# Sense_Plates.net
KiCad netlist of a schematic drawn in Altium Designer
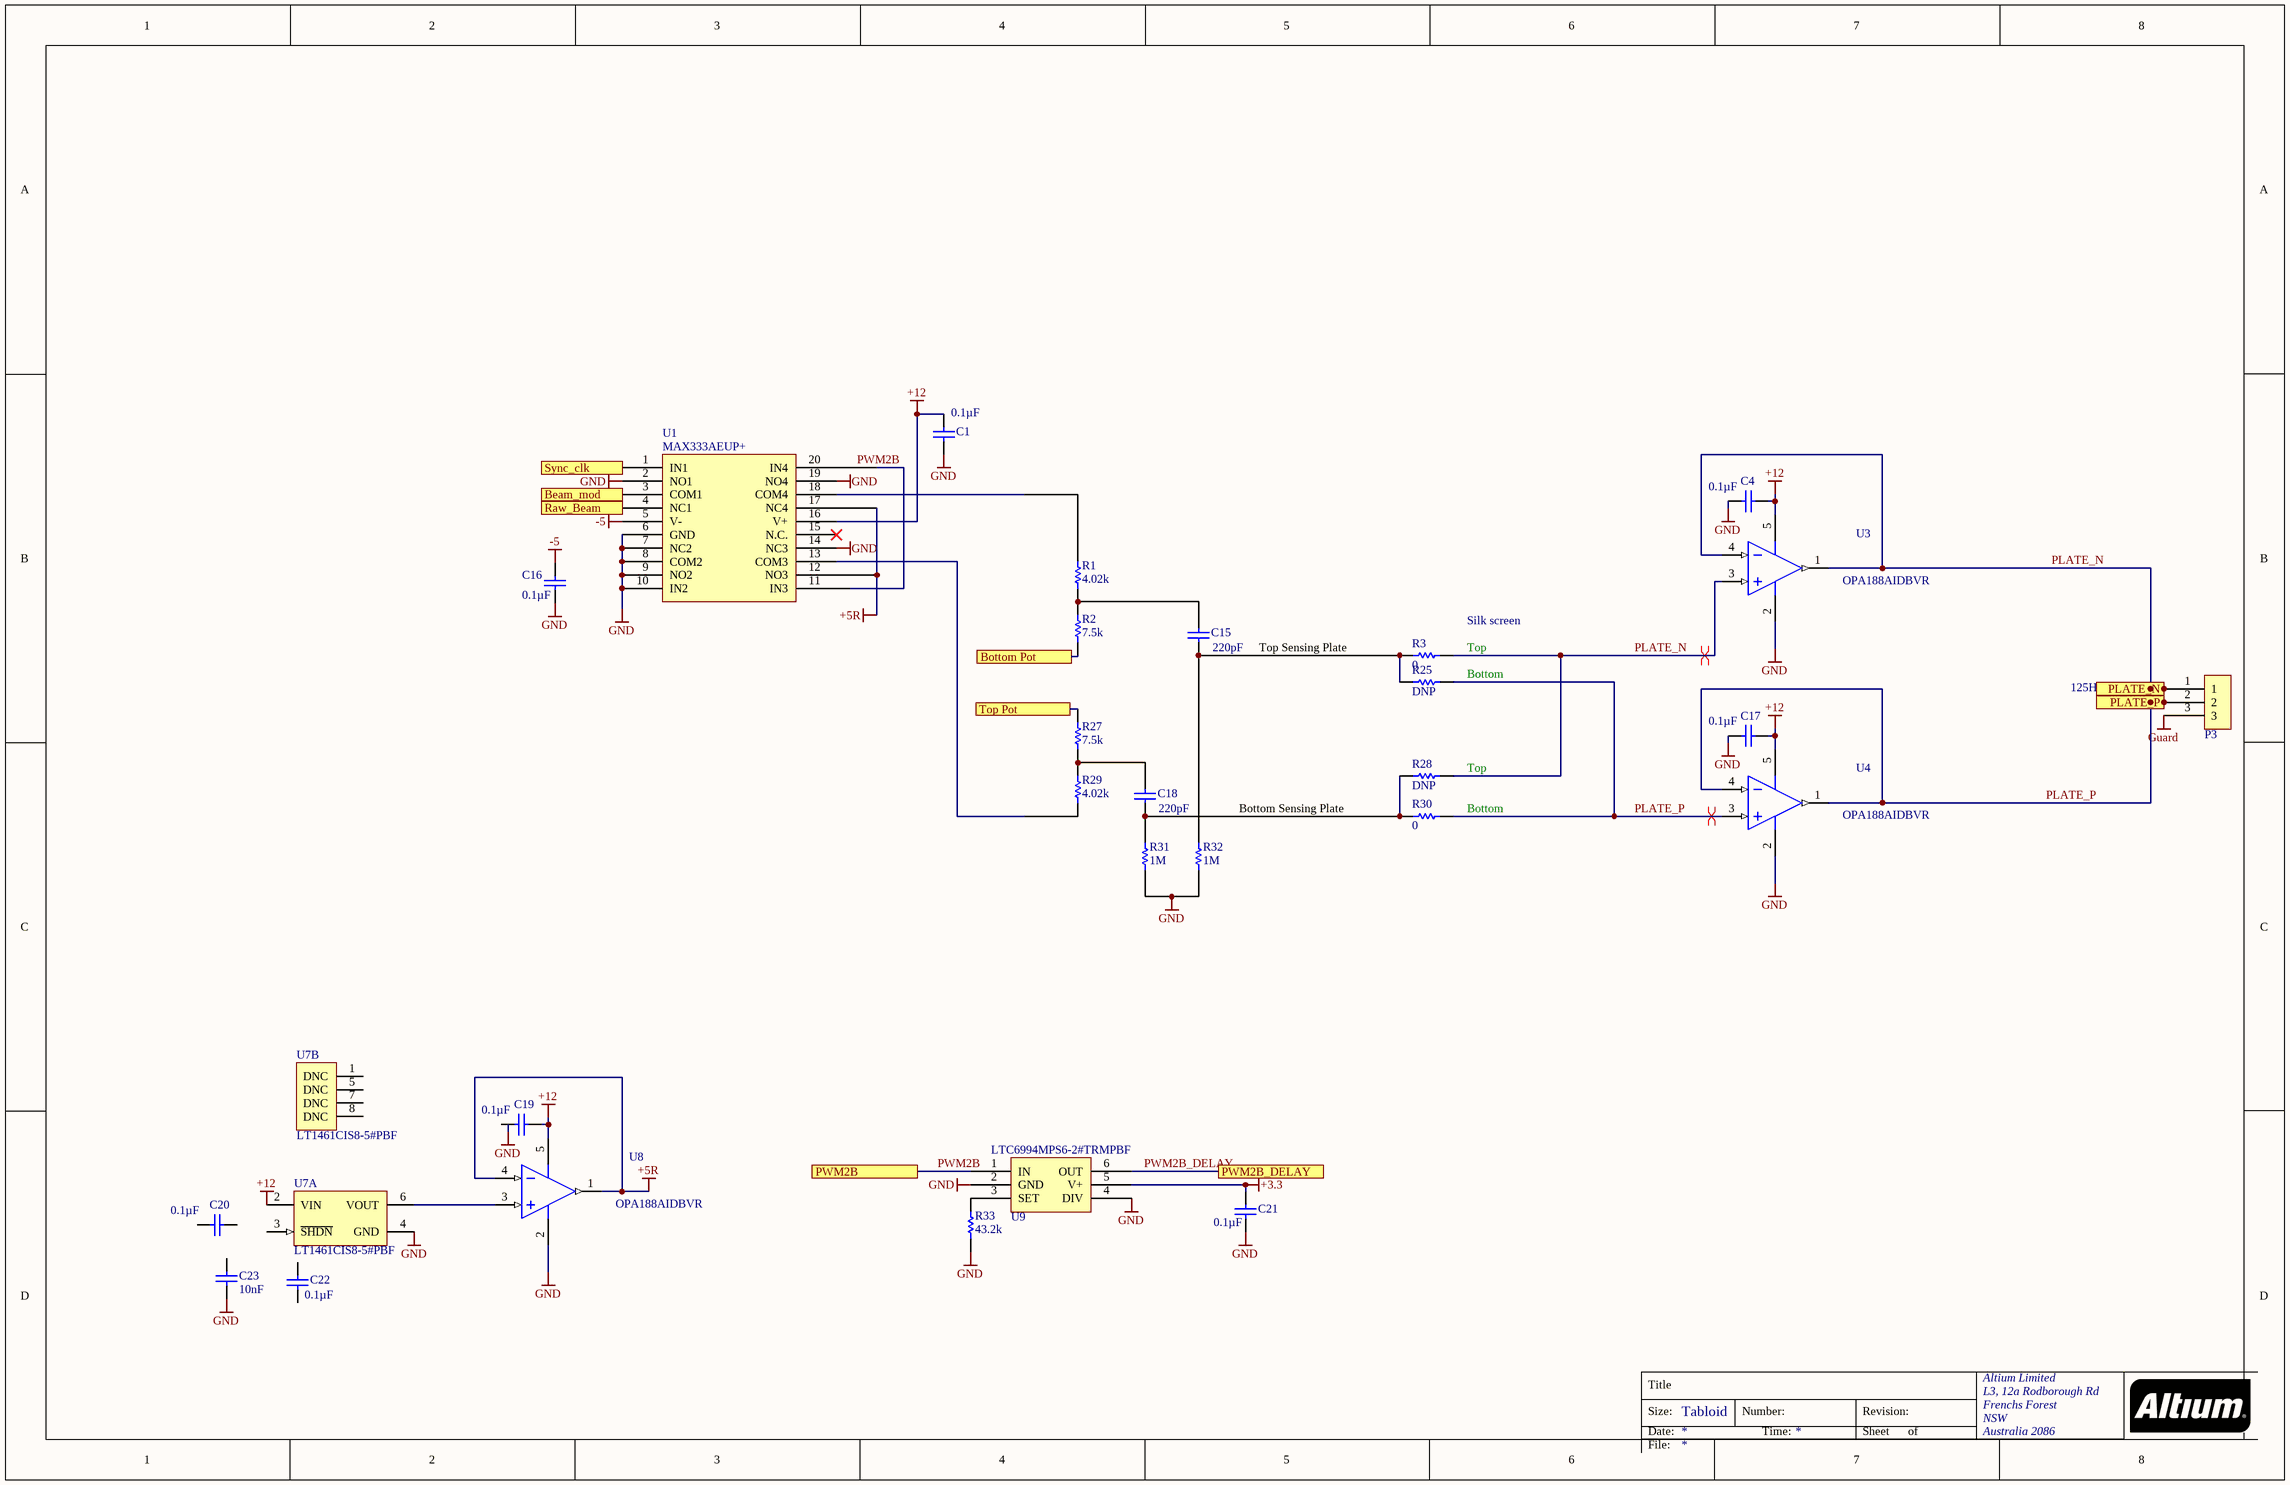
[diagram p0: Sense_Plates.SchDoc]

(export (version "E")
  (design (tool "Eeschema 10.0.6"))
  (components
    (comp (ref "C1")
      (value "CAP CER 0.1UF 25V X7R 0805")
      (footprint "CAPC0805(2012)145_N")
      (fields
        (field (name "MANUFACTURER") "Murata Electronics North America")
        (field (name "MANUFACTURER PART NUMBER") "GRM21BR71E104KA01L")
        (field (name "CAPACITANCE") "0.1µF")
        (field (name "TOLERANCE") "±10%")
      )
      (libsource (lib "Altium Content Vault") (part "CMP-1036-04795-1"))
    )
    (comp (ref "C4")
      (value "CAP CER 0.1UF 25V X7R 0805")
      (footprint "CAPC0805(2012)145_N")
      (fields
        (field (name "MANUFACTURER") "Murata Electronics North America")
        (field (name "MANUFACTURER PART NUMBER") "GRM21BR71E104KA01L")
        (field (name "CAPACITANCE") "0.1µF")
        (field (name "TOLERANCE") "±10%")
      )
      (libsource (lib "Altium Content Vault") (part "CMP-1036-04795-1"))
    )
    (comp (ref "C15")
      (value "CAP CER 1UF 25V X7R 0805")
      (footprint "CAPC0805(2012)155_L")
      (fields
        (field (name "MANUFACTURER") "Murata Electronics North America")
        (field (name "MANUFACTURER PART NUMBER") "GRM21BR71E105KA99L")
        (field (name "CAPACITANCE") "220pF")
        (field (name "TOLERANCE") "±10%")
      )
      (libsource (lib "Altium Content Vault") (part "CMP-1036-04882-1"))
    )
    (comp (ref "C16")
      (value "CAP CER 0.1UF 25V X7R 0805")
      (footprint "CAPC0805(2012)145_N")
      (fields
        (field (name "MANUFACTURER") "Murata Electronics North America")
        (field (name "MANUFACTURER PART NUMBER") "GRM21BR71E104KA01L")
        (field (name "CAPACITANCE") "0.1µF")
        (field (name "TOLERANCE") "±10%")
      )
      (libsource (lib "Altium Content Vault") (part "CMP-1036-04795-1"))
    )
    (comp (ref "C17")
      (value "CAP CER 0.1UF 25V X7R 0805")
      (footprint "CAPC0805(2012)145_N")
      (fields
        (field (name "MANUFACTURER") "Murata Electronics North America")
        (field (name "MANUFACTURER PART NUMBER") "GRM21BR71E104KA01L")
        (field (name "CAPACITANCE") "0.1µF")
        (field (name "TOLERANCE") "±10%")
      )
      (libsource (lib "Altium Content Vault") (part "CMP-1036-04795-1"))
    )
    (comp (ref "C18")
      (value "CAP CER 1UF 25V X7R 0805")
      (footprint "CAPC0805(2012)155_L")
      (fields
        (field (name "MANUFACTURER") "Murata Electronics North America")
        (field (name "MANUFACTURER PART NUMBER") "GRM21BR71E105KA99L")
        (field (name "CAPACITANCE") "220pF")
        (field (name "TOLERANCE") "±10%")
      )
      (libsource (lib "Altium Content Vault") (part "CMP-1036-04882-1"))
    )
    (comp (ref "C19")
      (value "CAP CER 0.1UF 25V X7R 0805")
      (footprint "CAPC0805(2012)145_N")
      (fields
        (field (name "MANUFACTURER") "Murata Electronics North America")
        (field (name "MANUFACTURER PART NUMBER") "GRM21BR71E104KA01L")
        (field (name "CAPACITANCE") "0.1µF")
        (field (name "TOLERANCE") "±10%")
      )
      (libsource (lib "Altium Content Vault") (part "CMP-1036-04795-1"))
    )
    (comp (ref "C20")
      (value "CAP CER 0.1UF 25V X7R 0805")
      (footprint "CAPC0805(2012)145_N")
      (fields
        (field (name "MANUFACTURER") "Murata Electronics North America")
        (field (name "MANUFACTURER PART NUMBER") "GRM21BR71E104KA01L")
        (field (name "CAPACITANCE") "0.1µF")
        (field (name "TOLERANCE") "±10%")
      )
      (libsource (lib "Altium Content Vault") (part "CMP-1036-04795-1"))
    )
    (comp (ref "C21")
      (value "CAP CER 0.1UF 25V X7R 0805")
      (footprint "CAPC0805(2012)145_N")
      (fields
        (field (name "MANUFACTURER") "Murata Electronics North America")
        (field (name "MANUFACTURER PART NUMBER") "GRM21BR71E104KA01L")
        (field (name "CAPACITANCE") "0.1µF")
        (field (name "TOLERANCE") "±10%")
      )
      (libsource (lib "Altium Content Vault") (part "CMP-1036-04795-1"))
    )
    (comp (ref "C22")
      (value "CAP CER 0.1UF 25V X7R 0805")
      (footprint "CAPC0805(2012)145_N")
      (fields
        (field (name "MANUFACTURER") "Murata Electronics North America")
        (field (name "MANUFACTURER PART NUMBER") "GRM21BR71E104KA01L")
        (field (name "CAPACITANCE") "0.1µF")
        (field (name "TOLERANCE") "±10%")
      )
      (libsource (lib "Altium Content Vault") (part "CMP-1036-04795-1"))
    )
    (comp (ref "C23")
      (value "Multilayer Ceramic Capacitors MLCC - SMD/SMT 0.01uF 50volts 10% X7R")
      (footprint "CAPC0805(2012)145_N")
      (fields
        (field (name "MANUFACTURER") "Kemet")
        (field (name "MANUFACTURER PART NUMBER") "C0805C103K5RACAUTO")
        (field (name "CAPACITANCE") "10nF")
        (field (name "TOLERANCE") "10%")
      )
      (libsource (lib "Altium Content Vault") (part "CMP-1036-04795-1"))
    )
    (comp (ref "P3")
      (value "Triax_Conn")
      (footprint "Triax_Conn")
      (libsource (lib "ZLS_Schematic_lib") (part "Triax_Conn"))
    )
    (comp (ref "R1")
      (value "4.02k")
      (footprint "RESC0402(1005)_M")
      (libsource (lib "Altium Content Vault") (part "CMP-1011-00463-1"))
    )
    (comp (ref "R2")
      (value "7.5k")
      (footprint "RESC0402(1005)_M")
      (libsource (lib "Altium Content Vault") (part "CMP-1011-00463-1"))
    )
    (comp (ref "R3")
      (value "0")
      (footprint "RESC0402(1005)_M")
      (libsource (lib "Altium Content Vault") (part "CMP-1011-00463-1"))
    )
    (comp (ref "R25")
      (value "DNP")
      (footprint "RESC0402(1005)_M")
      (libsource (lib "Altium Content Vault") (part "CMP-1011-00463-1"))
    )
    (comp (ref "R27")
      (value "7.5k")
      (footprint "RESC0402(1005)_M")
      (libsource (lib "Altium Content Vault") (part "CMP-1011-00463-1"))
    )
    (comp (ref "R28")
      (value "DNP")
      (footprint "RESC0402(1005)_M")
      (libsource (lib "Altium Content Vault") (part "CMP-1011-00463-1"))
    )
    (comp (ref "R29")
      (value "4.02k")
      (footprint "RESC0402(1005)_M")
      (libsource (lib "Altium Content Vault") (part "CMP-1011-00463-1"))
    )
    (comp (ref "R30")
      (value "0")
      (footprint "RESC0402(1005)_M")
      (libsource (lib "Altium Content Vault") (part "CMP-1011-00463-1"))
    )
    (comp (ref "R31")
      (value "1M")
      (footprint "RESC0402(1005)_M")
      (libsource (lib "Altium Content Vault") (part "CMP-1011-00463-1"))
    )
    (comp (ref "R32")
      (value "1M")
      (footprint "RESC0402(1005)_M")
      (libsource (lib "Altium Content Vault") (part "CMP-1011-00463-1"))
    )
    (comp (ref "R33")
      (value "43.2k")
      (footprint "RESC0402(1005)_M")
      (libsource (lib "Altium Content Vault") (part "CMP-1011-00463-1"))
    )
    (comp (ref "U1")
      (value "MAX333AEUP+")
      (footprint "TSOP65P640X90-20N")
      (description "IC SWITCH QUAD SPDT 20TSSOP")
      (fields (field (name "MANUFACTURER") "Maxim Integrated") (field (name "BASE PART NUMBER") "MAX333"))
      (libsource (lib "ZLS_Schematic_lib") (part "MAX333CWP+"))
    )
    (comp (ref "U3")
      (value "OPA188AIDBVR")
      (footprint "DBV0005A_M")
      (fields (field (name "MANUFACTURER") "Texas Instruments"))
      (libsource (lib "Altium Content Vault") (part "CMP-0809-00005-2"))
    )
    (comp (ref "U4")
      (value "OPA188AIDBVR")
      (footprint "DBV0005A_M")
      (fields (field (name "MANUFACTURER") "Texas Instruments"))
      (libsource (lib "Altium Content Vault") (part "CMP-0809-00005-2"))
    )
    (comp (ref "U7")
      (value "LT1461CIS8-5#PBF")
      (footprint "LT-S8-8_L")
      (description "Micropower Precision Low Dropout Voltage Reference, 5 V, -40 to 85 degC, 8-Pin SOIC, RoHS, Tube")
      (fields (field (name "TOLERANCE") "±0.08%") (field (name "MANUFACTURER") "Linear Technology"))
      (libsource (lib "Altium Content Vault") (part "LT-LT1461-S8"))
    )
    (comp (ref "U8")
      (value "OPA188AIDBVR")
      (footprint "DBV0005A_M")
      (fields (field (name "MANUFACTURER") "Texas Instruments"))
      (libsource (lib "Altium Content Vault") (part "CMP-0809-00005-2"))
    )
    (comp (ref "U9")
      (value "LTC6994MPS6-2#TRMPBF")
      (footprint "LTC6994MPS6-2#TRMPBF")
      (description "IC DELAY BLOCK 8TAP PROG TSOT23")
      (fields
        (field (name "MANUFACTURER") "Linear Technology/Analog Devices")
        (field (name "MANUFACTURER PART NUMBER") "LTC6994CS6-2#TRMPBF")
      )
      (libsource (lib "ZLS_Schematic_lib") (part "LTC6994MPS6-2#TRMPBF"))
    )
  )
  (nets
    (net (code "1") (name "+3.3") (class "Default")
      (node (ref "C21") (pin "1") (pinfunction "1_1") (pintype "passive"))
      (node (ref "U9") (pin "5") (pinfunction "V+_5") (pintype "passive"))
    )
    (net (code "2") (name "+5R") (class "Default")
      (node (ref "U1") (pin "12") (pinfunction "NO3_12") (pintype "passive"))
      (node (ref "U1") (pin "17") (pinfunction "NC4_17") (pintype "passive"))
      (node (ref "U8") (pin "1") (pinfunction "OUT_1") (pintype "output"))
      (node (ref "U8") (pin "4") (pinfunction "IN-_4") (pintype "input"))
    )
    (net (code "3") (name "+12") (class "Default")
      (node (ref "C1") (pin "1") (pinfunction "1_1") (pintype "passive"))
      (node (ref "C17") (pin "2") (pinfunction "2_2") (pintype "passive"))
      (node (ref "C19") (pin "2") (pinfunction "2_2") (pintype "passive"))
      (node (ref "C4") (pin "2") (pinfunction "2_2") (pintype "passive"))
      (node (ref "U1") (pin "16") (pinfunction "V+_16") (pintype "power_in"))
      (node (ref "U3") (pin "5") (pinfunction "V+_5") (pintype "power_in"))
      (node (ref "U4") (pin "5") (pinfunction "V+_5") (pintype "power_in"))
      (node (ref "U7") (pin "2") (pinfunction "VIN_2") (pintype "power_in"))
      (node (ref "U8") (pin "5") (pinfunction "V+_5") (pintype "power_in"))
    )
    (net (code "4") (name "-5") (class "Default")
      (node (ref "C16") (pin "1") (pinfunction "1_1") (pintype "passive"))
      (node (ref "U1") (pin "5") (pinfunction "V-_5") (pintype "power_in"))
    )
    (net (code "5") (name "/Beam_mod") (class "Default")
      (node (ref "U1") (pin "3") (pinfunction "COM1_3") (pintype "passive"))
    )
    (net (code "6") (name "/Bottom Pot") (class "Default")
      (node (ref "R2") (pin "1") (pinfunction "1_1") (pintype "passive"))
    )
    (net (code "7") (name "/PLATE_N") (class "Default")
      (node (ref "P3") (pin "1") (pinfunction "1_1") (pintype "passive"))
      (node (ref "R28") (pin "1") (pinfunction "1_1") (pintype "passive"))
      (node (ref "R3") (pin "1") (pinfunction "1_1") (pintype "passive"))
      (node (ref "U3") (pin "1") (pinfunction "OUT_1") (pintype "output"))
      (node (ref "U3") (pin "3") (pinfunction "IN+_3") (pintype "input"))
      (node (ref "U3") (pin "4") (pinfunction "IN-_4") (pintype "input"))
    )
    (net (code "8") (name "/PLATE_P") (class "Default")
      (node (ref "P3") (pin "2") (pinfunction "2_2") (pintype "passive"))
      (node (ref "R25") (pin "1") (pinfunction "1_1") (pintype "passive"))
      (node (ref "R30") (pin "1") (pinfunction "1_1") (pintype "passive"))
      (node (ref "U4") (pin "1") (pinfunction "OUT_1") (pintype "output"))
      (node (ref "U4") (pin "3") (pinfunction "IN+_3") (pintype "input"))
      (node (ref "U4") (pin "4") (pinfunction "IN-_4") (pintype "input"))
    )
    (net (code "9") (name "/PWM2B") (class "Default")
      (node (ref "U1") (pin "11") (pinfunction "IN3_11") (pintype "passive"))
      (node (ref "U1") (pin "20") (pinfunction "IN4_20") (pintype "passive"))
      (node (ref "U9") (pin "1") (pinfunction "IN_1") (pintype "passive"))
    )
    (net (code "10") (name "/PWM2B_DELAY") (class "Default")
      (node (ref "U9") (pin "6") (pinfunction "OUT_6") (pintype "passive"))
    )
    (net (code "11") (name "/Raw_Beam") (class "Default")
      (node (ref "U1") (pin "4") (pinfunction "NC1_4") (pintype "passive"))
    )
    (net (code "12") (name "/Sync_clk") (class "Default")
      (node (ref "U1") (pin "1") (pinfunction "IN1_1") (pintype "passive"))
    )
    (net (code "13") (name "/Top Pot") (class "Default")
      (node (ref "R27") (pin "2") (pinfunction "2_2") (pintype "passive"))
    )
    (net (code "14") (name "GND") (class "Default")
      (node (ref "C1") (pin "2") (pinfunction "2_2") (pintype "passive"))
      (node (ref "C16") (pin "2") (pinfunction "2_2") (pintype "passive"))
      (node (ref "C17") (pin "1") (pinfunction "1_1") (pintype "passive"))
      (node (ref "C21") (pin "2") (pinfunction "2_2") (pintype "passive"))
      (node (ref "C23") (pin "2") (pinfunction "2_2") (pintype "passive"))
      (node (ref "C4") (pin "1") (pinfunction "1_1") (pintype "passive"))
      (node (ref "R31") (pin "1") (pinfunction "1_1") (pintype "passive"))
      (node (ref "R32") (pin "1") (pinfunction "1_1") (pintype "passive"))
      (node (ref "R33") (pin "1") (pinfunction "1_1") (pintype "passive"))
      (node (ref "U1") (pin "10") (pinfunction "IN2_10") (pintype "passive"))
      (node (ref "U1") (pin "14") (pinfunction "NC3_14") (pintype "passive"))
      (node (ref "U1") (pin "19") (pinfunction "NO4_19") (pintype "passive"))
      (node (ref "U1") (pin "2") (pinfunction "NO1_2") (pintype "passive"))
      (node (ref "U1") (pin "6") (pinfunction "GND_6") (pintype "passive"))
      (node (ref "U1") (pin "7") (pinfunction "NC2_7") (pintype "passive"))
      (node (ref "U1") (pin "8") (pinfunction "COM2_8") (pintype "passive"))
      (node (ref "U1") (pin "9") (pinfunction "NO2_9") (pintype "passive"))
      (node (ref "U3") (pin "2") (pinfunction "V-_2") (pintype "power_in"))
      (node (ref "U4") (pin "2") (pinfunction "V-_2") (pintype "power_in"))
      (node (ref "U7") (pin "4") (pinfunction "GND_4") (pintype "power_in"))
      (node (ref "U8") (pin "2") (pinfunction "V-_2") (pintype "power_in"))
      (node (ref "U9") (pin "2") (pinfunction "GND_2") (pintype "passive"))
      (node (ref "U9") (pin "4") (pinfunction "DIV_4") (pintype "passive"))
    )
    (net (code "15") (name "Guard") (class "Default")
      (node (ref "P3") (pin "3") (pinfunction "3_3") (pintype "passive"))
    )
    (net (code "16") (name "Net-(C15-Pad1)") (class "Default")
      (node (ref "C15") (pin "1") (pinfunction "1_1") (pintype "passive"))
      (node (ref "R25") (pin "2") (pinfunction "2_2") (pintype "passive"))
      (node (ref "R3") (pin "2") (pinfunction "2_2") (pintype "passive"))
      (node (ref "R32") (pin "2") (pinfunction "2_2") (pintype "passive"))
    )
    (net (code "17") (name "Net-(C15-Pad2)") (class "Default")
      (node (ref "C15") (pin "2") (pinfunction "2_2") (pintype "passive"))
      (node (ref "R1") (pin "1") (pinfunction "1_1") (pintype "passive"))
      (node (ref "R2") (pin "2") (pinfunction "2_2") (pintype "passive"))
    )
    (net (code "18") (name "Net-(C18-Pad1)") (class "Default")
      (node (ref "C18") (pin "1") (pinfunction "1_1") (pintype "passive"))
      (node (ref "R28") (pin "2") (pinfunction "2_2") (pintype "passive"))
      (node (ref "R30") (pin "2") (pinfunction "2_2") (pintype "passive"))
      (node (ref "R31") (pin "2") (pinfunction "2_2") (pintype "passive"))
    )
    (net (code "19") (name "Net-(C18-Pad2)") (class "Default")
      (node (ref "C18") (pin "2") (pinfunction "2_2") (pintype "passive"))
      (node (ref "R27") (pin "1") (pinfunction "1_1") (pintype "passive"))
      (node (ref "R29") (pin "2") (pinfunction "2_2") (pintype "passive"))
    )
    (net (code "20") (name "Net-(U1-COM3)") (class "Default")
      (node (ref "R29") (pin "1") (pinfunction "1_1") (pintype "passive"))
      (node (ref "U1") (pin "13") (pinfunction "COM3_13") (pintype "passive"))
    )
    (net (code "21") (name "Net-(U1-COM4)") (class "Default")
      (node (ref "R1") (pin "2") (pinfunction "2_2") (pintype "passive"))
      (node (ref "U1") (pin "18") (pinfunction "COM4_18") (pintype "passive"))
    )
    (net (code "22") (name "Net-(U7A-VOUT)") (class "Default")
      (node (ref "U7") (pin "6") (pinfunction "VOUT_6") (pintype "power_in"))
      (node (ref "U8") (pin "3") (pinfunction "IN+_3") (pintype "input"))
    )
    (net (code "23") (name "Net-(U9-SET)") (class "Default")
      (node (ref "R33") (pin "2") (pinfunction "2_2") (pintype "passive"))
      (node (ref "U9") (pin "3") (pinfunction "SET_3") (pintype "passive"))
    )
    (net (code "24") (name "unconnected-(C19-Pad1)") (class "Default")
      (node (ref "C19") (pin "1") (pinfunction "1_1") (pintype "passive"))
    )
    (net (code "25") (name "unconnected-(C20-Pad1)") (class "Default")
      (node (ref "C20") (pin "1") (pinfunction "1_1") (pintype "passive"))
    )
    (net (code "26") (name "unconnected-(C20-Pad2)") (class "Default")
      (node (ref "C20") (pin "2") (pinfunction "2_2") (pintype "passive"))
    )
    (net (code "27") (name "unconnected-(C22-Pad1)") (class "Default")
      (node (ref "C22") (pin "1") (pinfunction "1_1") (pintype "passive"))
    )
    (net (code "28") (name "unconnected-(C22-Pad2)") (class "Default")
      (node (ref "C22") (pin "2") (pinfunction "2_2") (pintype "passive"))
    )
    (net (code "29") (name "unconnected-(C23-Pad1)") (class "Default")
      (node (ref "C23") (pin "1") (pinfunction "1_1") (pintype "passive"))
    )
    (net (code "30") (name "unconnected-(U1-N.C.-Pad15)") (class "Default")
      (node (ref "U1") (pin "15") (pinfunction "N.C._15") (pintype "passive+no_connect"))
    )
    (net (code "31") (name "unconnected-(U7A-~{SHDN}-Pad3)") (class "Default")
      (node (ref "U7") (pin "3") (pinfunction "~{SHDN}_3") (pintype "input"))
    )
    (net (code "32") (name "unconnected-(U7B-DNC-Pad1)") (class "Default")
      (node (ref "U7") (pin "1") (pinfunction "DNC_1") (pintype "passive"))
    )
    (net (code "33") (name "unconnected-(U7B-DNC-Pad5)") (class "Default")
      (node (ref "U7") (pin "5") (pinfunction "DNC_5") (pintype "passive"))
    )
    (net (code "34") (name "unconnected-(U7B-DNC-Pad7)") (class "Default")
      (node (ref "U7") (pin "7") (pinfunction "DNC_7") (pintype "passive"))
    )
    (net (code "35") (name "unconnected-(U7B-DNC-Pad8)") (class "Default")
      (node (ref "U7") (pin "8") (pinfunction "DNC_8") (pintype "passive"))
    )
  )
)
